# HGD_v0_2_-20200615.net
KiCad netlist of a schematic drawn in Altium Designer
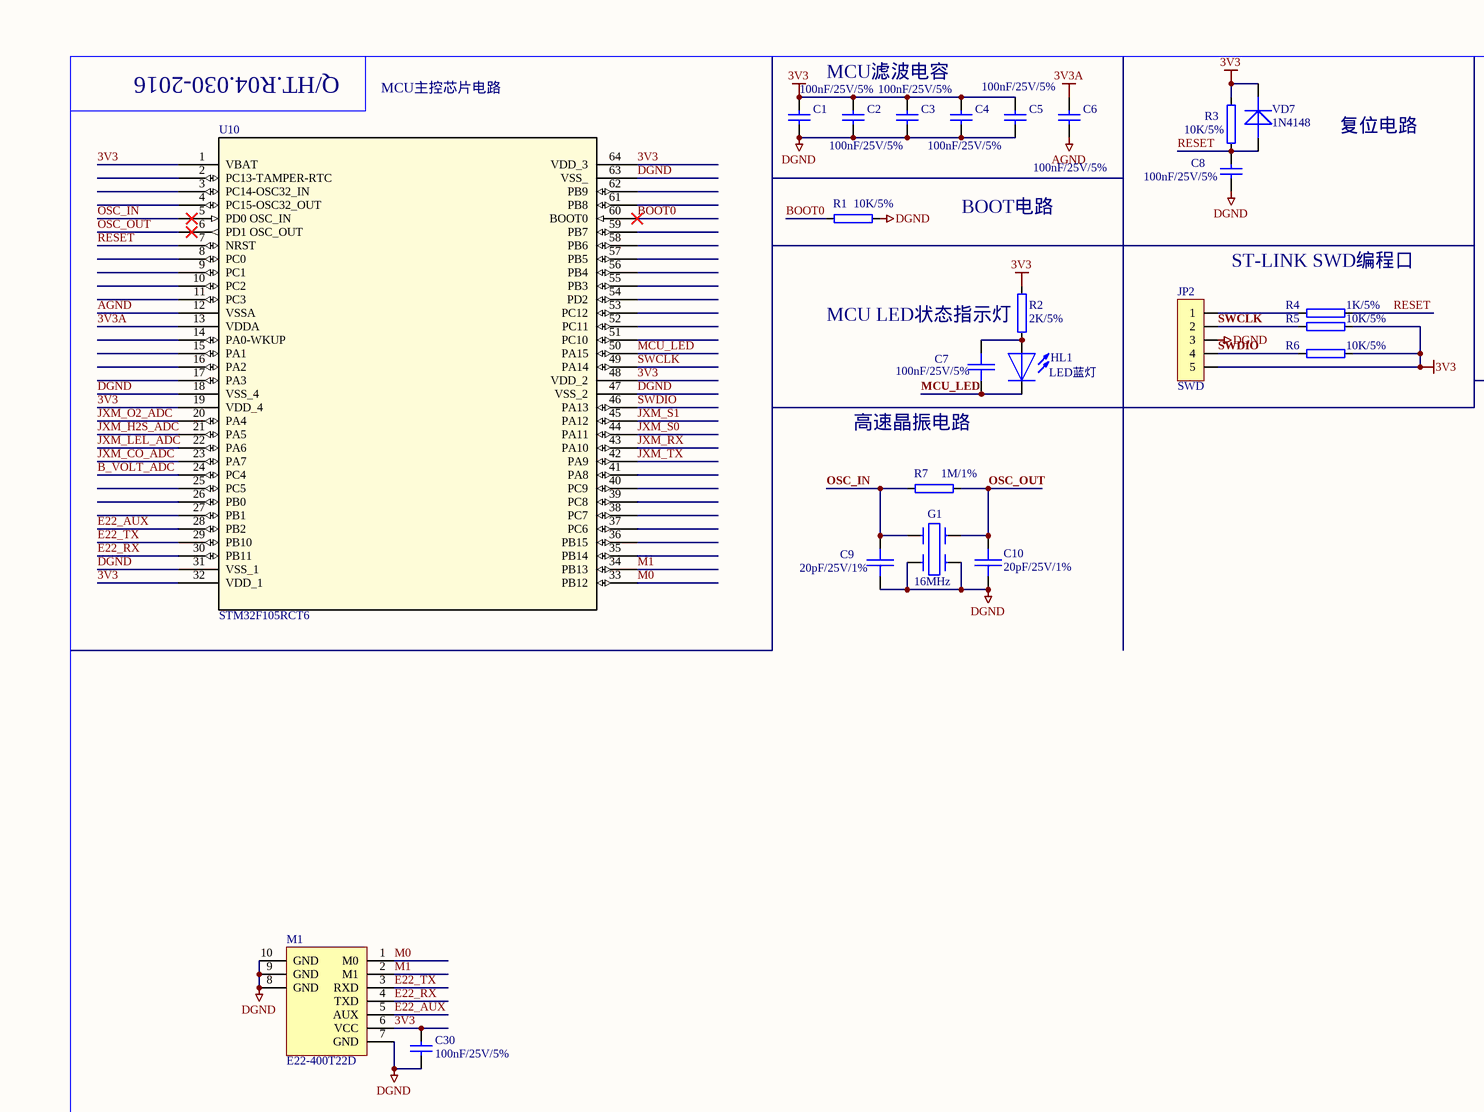
[diagram p0: HGD(v0.2)-20200615.SchDoc, top left]
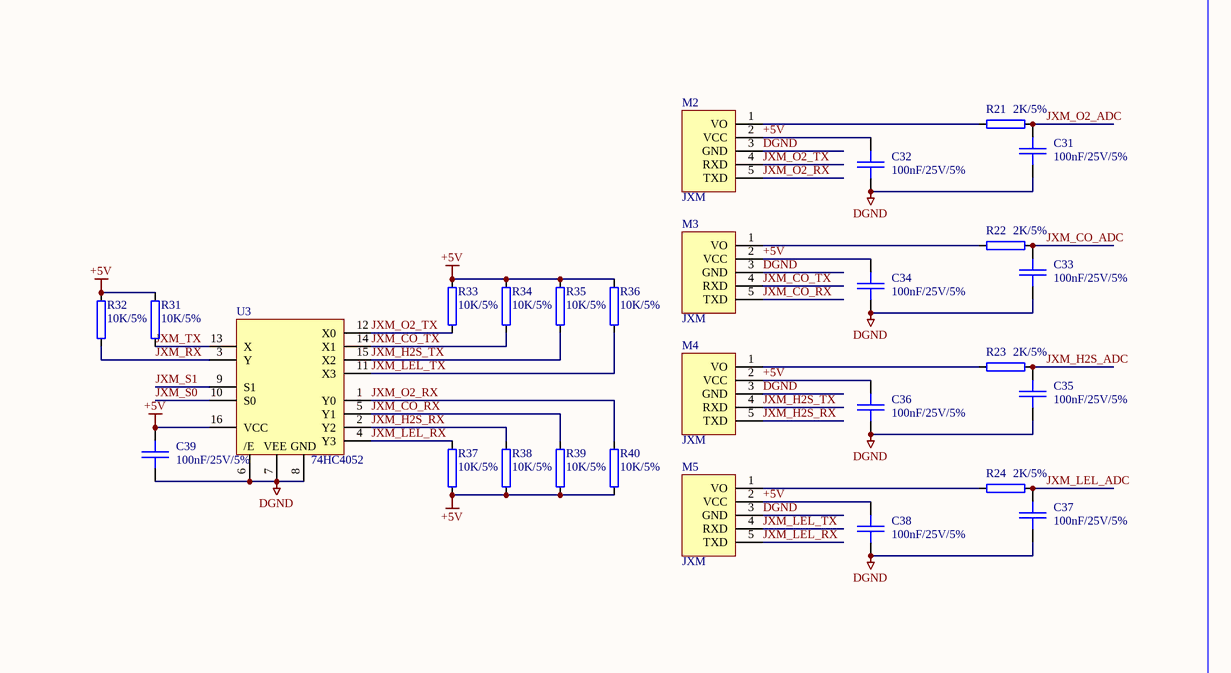
[diagram p1: HGD(v0.2)-20200615.SchDoc, top right]
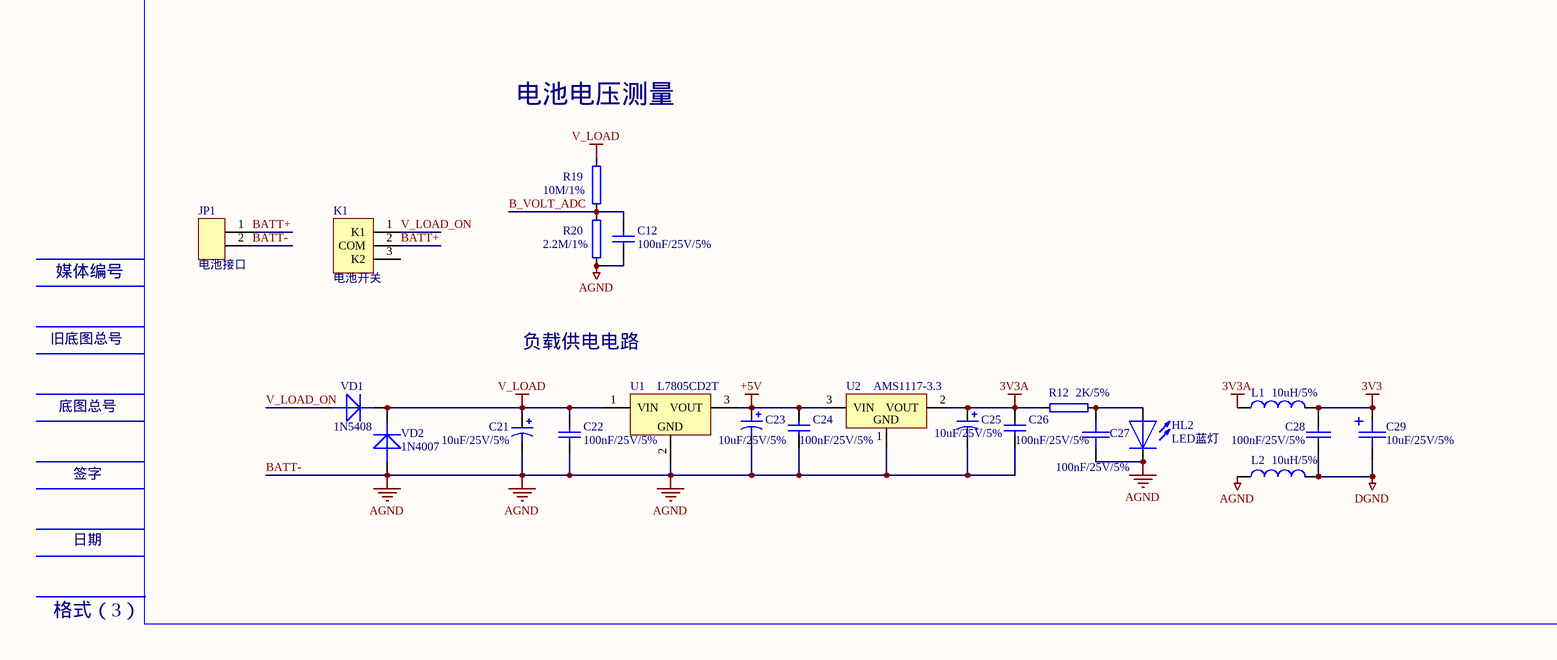
[diagram p2: HGD(v0.2)-20200615.SchDoc, bottom left]
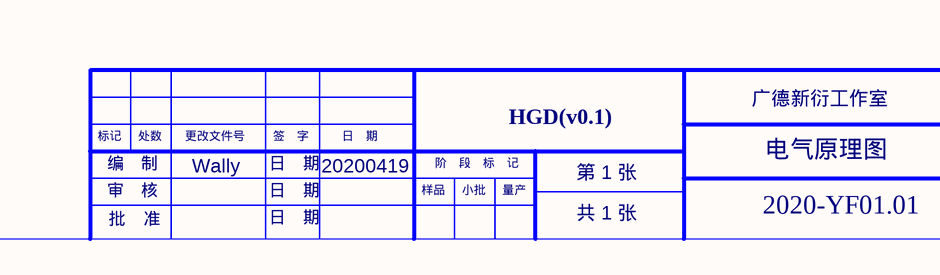
[diagram p3: HGD(v0.2)-20200615.SchDoc, bottom right]

(export (version "E")
  (design (tool "Eeschema 10.0.6"))
  (components
    (comp (ref "C1")
      (value "100nF/25V/5%")
      (footprint "C0603")
      (description "电容")
      (libsource (lib "*") (part "CAP-SMD"))
    )
    (comp (ref "C2")
      (value "100nF/25V/5%")
      (footprint "C0603")
      (description "电容")
      (libsource (lib "*") (part "CAP-SMD"))
    )
    (comp (ref "C3")
      (value "100nF/25V/5%")
      (footprint "C0603")
      (description "电容")
      (libsource (lib "*") (part "CAP-SMD"))
    )
    (comp (ref "C4")
      (value "100nF/25V/5%")
      (footprint "C0603")
      (description "电容")
      (libsource (lib "*") (part "CAP-SMD"))
    )
    (comp (ref "C5")
      (value "100nF/25V/5%")
      (footprint "C0603")
      (description "电容")
      (libsource (lib "*") (part "CAP-SMD"))
    )
    (comp (ref "C6")
      (value "100nF/25V/5%")
      (footprint "C0603")
      (description "电容")
      (libsource (lib "*") (part "CAP-SMD"))
    )
    (comp (ref "C7")
      (value "100nF/25V/5%")
      (footprint "C0603")
      (description "电容")
      (libsource (lib "*") (part "CAP"))
    )
    (comp (ref "C8")
      (value "100nF/25V/5%")
      (footprint "C0603")
      (description "电容")
      (libsource (lib "*") (part "CAP-SMD"))
    )
    (comp (ref "C9")
      (value "20pF/25V/1%")
      (footprint "C0603")
      (description "电容")
      (libsource (lib "ESSCH-Union") (part "CAP"))
    )
    (comp (ref "C10")
      (value "20pF/25V/1%")
      (footprint "C0603")
      (description "电容")
      (libsource (lib "ESSCH-Union") (part "CAP"))
    )
    (comp (ref "C12") (value "100nF/25V/5%") (footprint "C0603") (libsource (lib "*") (part "CAP-SMD")))
    (comp (ref "C21")
      (value "10uF/25V/5%")
      (footprint "C1206-1")
      (description "钽电容")
      (fields (field (name "PUBLISHER") "Altium Limited"))
      (libsource (lib "Miscellaneous Devices") (part "Cap Pol1"))
    )
    (comp (ref "C22")
      (value "100nF/25V/5%")
      (footprint "C0603")
      (description "电容")
      (fields (field (name "PUBLISHER") "Altium Limited"))
      (libsource (lib "Miscellaneous Devices") (part "Cap"))
    )
    (comp (ref "C23")
      (value "10uF/25V/5%")
      (footprint "C1206-1")
      (description "钽电容")
      (fields (field (name "PUBLISHER") "Altium Limited"))
      (libsource (lib "Miscellaneous Devices") (part "Cap Pol1"))
    )
    (comp (ref "C24")
      (value "100nF/25V/5%")
      (footprint "C0603")
      (description "电容")
      (fields (field (name "PUBLISHER") "Altium Limited"))
      (libsource (lib "Miscellaneous Devices") (part "Cap"))
    )
    (comp (ref "C25")
      (value "10uF/25V/5%")
      (footprint "C1206-1")
      (description "钽电容")
      (fields (field (name "PUBLISHER") "Altium Limited"))
      (libsource (lib "Miscellaneous Devices") (part "Cap Pol1"))
    )
    (comp (ref "C26")
      (value "100nF/25V/5%")
      (footprint "C0603")
      (description "电容")
      (fields (field (name "PUBLISHER") "Altium Limited"))
      (libsource (lib "Miscellaneous Devices") (part "Cap"))
    )
    (comp (ref "C27")
      (value "100nF/25V/5%")
      (footprint "C0603")
      (description "电容")
      (libsource (lib "*") (part "CAP"))
    )
    (comp (ref "C28")
      (value "100nF/25V/5%")
      (footprint "C0603")
      (description "电容")
      (libsource (lib "") (part "CAP_1"))
    )
    (comp (ref "C29")
      (value "10uF/25V/5%")
      (footprint "C1206-1")
      (description "钽电容")
      (libsource (lib "*") (part "ELECTRO1"))
    )
    (comp (ref "C30")
      (value "100nF/25V/5%")
      (footprint "C0603")
      (description "电容")
      (fields (field (name "PUBLISHER") "Altium Limited"))
      (libsource (lib "Miscellaneous Devices") (part "Cap"))
    )
    (comp (ref "C31")
      (value "100nF/25V/5%")
      (footprint "C0603")
      (description "电容")
      (libsource (lib "*") (part "CAP"))
    )
    (comp (ref "C32")
      (value "100nF/25V/5%")
      (footprint "C0603")
      (description "电容")
      (libsource (lib "*") (part "CAP"))
    )
    (comp (ref "C33")
      (value "100nF/25V/5%")
      (footprint "C0603")
      (description "电容")
      (libsource (lib "*") (part "CAP"))
    )
    (comp (ref "C34")
      (value "100nF/25V/5%")
      (footprint "C0603")
      (description "电容")
      (libsource (lib "*") (part "CAP"))
    )
    (comp (ref "C35")
      (value "100nF/25V/5%")
      (footprint "C0603")
      (description "电容")
      (libsource (lib "*") (part "CAP"))
    )
    (comp (ref "C36")
      (value "100nF/25V/5%")
      (footprint "C0603")
      (description "电容")
      (libsource (lib "*") (part "CAP"))
    )
    (comp (ref "C37")
      (value "100nF/25V/5%")
      (footprint "C0603")
      (description "电容")
      (libsource (lib "*") (part "CAP"))
    )
    (comp (ref "C38")
      (value "100nF/25V/5%")
      (footprint "C0603")
      (description "电容")
      (libsource (lib "*") (part "CAP"))
    )
    (comp (ref "C39")
      (value "100nF/25V/5%")
      (footprint "C0603")
      (description "电容")
      (libsource (lib "*") (part "CAP"))
    )
    (comp (ref "G1")
      (value "16MHz")
      (footprint "OSC5032")
      (description "两对电极压电晶体")
      (libsource (lib "ESSCH-Union") (part "CRYSTAL_4"))
    )
    (comp (ref "HL1")
      (value "LED蓝灯")
      (footprint "LED0603")
      (description "发光二极管")
      (libsource (lib "wypPCB_Lib") (part "发光二极管"))
    )
    (comp (ref "HL2")
      (value "LED蓝灯")
      (footprint "LED0603")
      (description "发光二极管")
      (libsource (lib "wypPCB_Lib") (part "发光二极管"))
    )
    (comp (ref "JP1")
      (value "电池接口")
      (footprint "XH2.54-LI-2P")
      (description "XH2.54-2P/PH2.0-2P插座")
      (libsource (lib "wypPCB_Lib") (part "XH2.54-2P/PH2.0-2P"))
    )
    (comp (ref "JP2")
      (value "SWD")
      (footprint "XH2.54-5AW")
      (description "XH2.54-5P直插插针")
      (libsource (lib "wypPCB_Lib") (part "JP_XH2.54-5AW"))
    )
    (comp (ref "K1")
      (value "电池开关")
      (footprint "SK-12D07")
      (description "SK-12D07：3脚2档小型拨动开关")
      (libsource (lib "wypPCB_Lib") (part "SK-12D07"))
    )
    (comp (ref "L1")
      (value "10uH/5%")
      (footprint "L0603")
      (description "电感")
      (libsource (lib "wypPCB_Lib") (part "电感"))
    )
    (comp (ref "L2")
      (value "10uH/5%")
      (footprint "L0603")
      (description "电感")
      (libsource (lib "wypPCB_Lib") (part "电感"))
    )
    (comp (ref "M1")
      (value "E22-400T22D")
      (footprint "E22-400T22D")
      (description "E22-400T22D LoRa模块")
      (libsource (lib "wypPCB_Lib") (part "E22-400T22D"))
    )
    (comp (ref "M2")
      (value "JXM")
      (footprint "JXM")
      (description "JXM智能气体模组传感器")
      (libsource (lib "wypPCB_Lib") (part "JXM"))
    )
    (comp (ref "M3")
      (value "JXM")
      (footprint "JXM")
      (description "JXM智能气体模组传感器")
      (libsource (lib "wypPCB_Lib") (part "JXM"))
    )
    (comp (ref "M4")
      (value "JXM")
      (footprint "JXM")
      (description "JXM智能气体模组传感器")
      (libsource (lib "wypPCB_Lib") (part "JXM"))
    )
    (comp (ref "M5")
      (value "JXM")
      (footprint "JXM")
      (description "JXM智能气体模组传感器")
      (libsource (lib "wypPCB_Lib") (part "JXM"))
    )
    (comp (ref "R1")
      (value "10K/5%")
      (footprint "R0603")
      (description "电阻")
      (libsource (lib "") (part "RES2_2"))
    )
    (comp (ref "R2")
      (value "2K/5%")
      (footprint "R0603")
      (description "电阻")
      (libsource (lib "") (part "RES2_2"))
    )
    (comp (ref "R3")
      (value "10K/5%")
      (footprint "R0603")
      (description "电阻")
      (libsource (lib "*") (part "RES2"))
    )
    (comp (ref "R4")
      (value "1K/5%")
      (footprint "R0603")
      (description "电阻")
      (libsource (lib "*") (part "RES2"))
    )
    (comp (ref "R5")
      (value "10K/5%")
      (footprint "R0603")
      (description "电阻")
      (libsource (lib "*") (part "RES2"))
    )
    (comp (ref "R6")
      (value "10K/5%")
      (footprint "R0603")
      (description "电阻")
      (libsource (lib "*") (part "RES2"))
    )
    (comp (ref "R7")
      (value "1M/1%")
      (footprint "R0603")
      (description "电阻")
      (libsource (lib "*") (part "RES2"))
    )
    (comp (ref "R12")
      (value "2K/5%")
      (footprint "R0603")
      (description "电阻")
      (libsource (lib "") (part "RES2_2"))
    )
    (comp (ref "R19")
      (value "10M/1%")
      (footprint "R0603")
      (description "电阻")
      (libsource (lib "") (part "RES2_2"))
    )
    (comp (ref "R20")
      (value "2.2M/1%")
      (footprint "R0603")
      (description "电阻")
      (libsource (lib "") (part "RES2_2"))
    )
    (comp (ref "R21")
      (value "2K/5%")
      (footprint "R0603")
      (description "电阻")
      (libsource (lib "") (part "RES2_2"))
    )
    (comp (ref "R22")
      (value "2K/5%")
      (footprint "R0603")
      (description "电阻")
      (libsource (lib "") (part "RES2_2"))
    )
    (comp (ref "R23")
      (value "2K/5%")
      (footprint "R0603")
      (description "电阻")
      (libsource (lib "") (part "RES2_2"))
    )
    (comp (ref "R24")
      (value "2K/5%")
      (footprint "R0603")
      (description "电阻")
      (libsource (lib "") (part "RES2_2"))
    )
    (comp (ref "R31")
      (value "10K/5%")
      (footprint "R0603")
      (description "电阻")
      (libsource (lib "") (part "RES2_1"))
    )
    (comp (ref "R32")
      (value "10K/5%")
      (footprint "R0603")
      (description "电阻")
      (libsource (lib "") (part "RES2_1"))
    )
    (comp (ref "R33")
      (value "10K/5%")
      (footprint "R0603")
      (description "电阻")
      (libsource (lib "") (part "RES2_1"))
    )
    (comp (ref "R34")
      (value "10K/5%")
      (footprint "R0603")
      (description "电阻")
      (libsource (lib "") (part "RES2_1"))
    )
    (comp (ref "R35")
      (value "10K/5%")
      (footprint "R0603")
      (description "电阻")
      (libsource (lib "") (part "RES2_1"))
    )
    (comp (ref "R36")
      (value "10K/5%")
      (footprint "R0603")
      (description "电阻")
      (libsource (lib "") (part "RES2_1"))
    )
    (comp (ref "R37")
      (value "10K/5%")
      (footprint "R0603")
      (description "电阻")
      (libsource (lib "") (part "RES2_1"))
    )
    (comp (ref "R38")
      (value "10K/5%")
      (footprint "R0603")
      (description "电阻")
      (libsource (lib "") (part "RES2_1"))
    )
    (comp (ref "R39")
      (value "10K/5%")
      (footprint "R0603")
      (description "电阻")
      (libsource (lib "") (part "RES2_1"))
    )
    (comp (ref "R40")
      (value "10K/5%")
      (footprint "R0603")
      (description "电阻")
      (libsource (lib "") (part "RES2_1"))
    )
    (comp (ref "U1")
      (value "L7805CD2T")
      (footprint "D2PAK")
      (description "Positive voltage regulator")
      (libsource (lib "wypPCB_Lib") (part "L7805CD2T"))
    )
    (comp (ref "U2")
      (value "AMS1117-3.3")
      (footprint "SOT230P700X180-4N")
      (description "U_AMS1117稳压芯片")
      (libsource (lib "wypPCB_Lib") (part "U_AMS1117"))
    )
    (comp (ref "U3")
      (value "74HC4052")
      (footprint "SO16_74HC4052")
      (libsource (lib "wypPCB_Lib") (part "74HC4052"))
    )
    (comp (ref "U10")
      (value "STM32F105RCT6")
      (footprint "LQFP64")
      (description "MCU")
      (fields
        (field (name "MANUFACTURER_PART_NUMBER") "STM32F103RCT6")
        (field (name "DIGIKEYPARTNUMBER") "497-9033-ND")
        (field (name "COPYRIGHT") "Copyright (C) 2015 Accelerated Designs. All rights reserved")
      )
      (libsource (lib "L14-Collect_board(v1.1)") (part "STM32F103RCT6"))
    )
    (comp (ref "VD1")
      (value "1N5408")
      (footprint "SMA_DO-214AC")
      (description "开关二极管")
      (libsource (lib "wypPCB_Lib") (part "开关二极管"))
    )
    (comp (ref "VD2")
      (value "1N4007")
      (footprint "SMA_DO-214AC")
      (description "开关二极管")
      (libsource (lib "wypPCB_Lib") (part "开关二极管"))
    )
    (comp (ref "VD7")
      (value "1N4148")
      (footprint "LL-34")
      (description "开关二极管")
      (libsource (lib "wypPCB_Lib") (part "开关二极管"))
    )
  )
  (nets
    (net (code "1") (name "+5V") (class "Default")
      (node (ref "C23") (pin "1") (pinfunction "1_1") (pintype "passive"))
      (node (ref "C24") (pin "2") (pinfunction "2_2") (pintype "passive"))
      (node (ref "C32") (pin "1") (pintype "passive"))
      (node (ref "C34") (pin "1") (pintype "passive"))
      (node (ref "C36") (pin "1") (pintype "passive"))
      (node (ref "C38") (pin "1") (pintype "passive"))
      (node (ref "C39") (pin "1") (pintype "passive"))
      (node (ref "M2") (pin "2") (pinfunction "VCC_2") (pintype "passive"))
      (node (ref "M3") (pin "2") (pinfunction "VCC_2") (pintype "passive"))
      (node (ref "M4") (pin "2") (pinfunction "VCC_2") (pintype "passive"))
      (node (ref "M5") (pin "2") (pinfunction "VCC_2") (pintype "passive"))
      (node (ref "R31") (pin "2") (pintype "passive"))
      (node (ref "R32") (pin "2") (pintype "passive"))
      (node (ref "R33") (pin "2") (pintype "passive"))
      (node (ref "R34") (pin "2") (pintype "passive"))
      (node (ref "R35") (pin "2") (pintype "passive"))
      (node (ref "R36") (pin "2") (pintype "passive"))
      (node (ref "R37") (pin "1") (pintype "passive"))
      (node (ref "R38") (pin "1") (pintype "passive"))
      (node (ref "R39") (pin "1") (pintype "passive"))
      (node (ref "R40") (pin "1") (pintype "passive"))
      (node (ref "U1") (pin "3") (pinfunction "VOUT_3") (pintype "passive"))
      (node (ref "U2") (pin "3") (pinfunction "VIN_3") (pintype "passive"))
      (node (ref "U3") (pin "16") (pinfunction "VCC_16") (pintype "passive"))
    )
    (net (code "2") (name "/BATT+") (class "Default")
      (node (ref "JP1") (pin "1") (pintype "passive"))
      (node (ref "K1") (pin "2") (pinfunction "COM_2") (pintype "passive"))
    )
    (net (code "3") (name "/BOOT0") (class "Default")
      (node (ref "R1") (pin "2") (pintype "passive"))
      (node (ref "U10") (pin "60") (pinfunction "BOOT0_60") (pintype "input"))
    )
    (net (code "4") (name "/B_VOLT_ADC") (class "Default")
      (node (ref "C12") (pin "1") (pintype "passive"))
      (node (ref "R19") (pin "2") (pintype "passive"))
      (node (ref "R20") (pin "1") (pintype "passive"))
      (node (ref "U10") (pin "24") (pinfunction "PC4_24") (pintype "bidirectional"))
    )
    (net (code "5") (name "/E22_AUX") (class "Default")
      (node (ref "M1") (pin "5") (pinfunction "AUX_5") (pintype "passive"))
      (node (ref "U10") (pin "28") (pinfunction "PB2_28") (pintype "bidirectional"))
    )
    (net (code "6") (name "/E22_RX") (class "Default")
      (node (ref "M1") (pin "4") (pinfunction "TXD_4") (pintype "passive"))
      (node (ref "U10") (pin "30") (pinfunction "PB11_30") (pintype "bidirectional"))
    )
    (net (code "7") (name "/E22_TX") (class "Default")
      (node (ref "M1") (pin "3") (pinfunction "RXD_3") (pintype "passive"))
      (node (ref "U10") (pin "29") (pinfunction "PB10_29") (pintype "bidirectional"))
    )
    (net (code "8") (name "/JXM_CO_ADC") (class "Default")
      (node (ref "C33") (pin "1") (pintype "passive"))
      (node (ref "R22") (pin "1") (pintype "passive"))
      (node (ref "U10") (pin "23") (pinfunction "PA7_23") (pintype "bidirectional"))
    )
    (net (code "9") (name "/JXM_CO_RX") (class "Default")
      (node (ref "M3") (pin "5") (pinfunction "TXD_5") (pintype "passive"))
      (node (ref "R39") (pin "2") (pintype "passive"))
      (node (ref "U3") (pin "5") (pinfunction "Y1_5") (pintype "passive"))
    )
    (net (code "10") (name "/JXM_CO_TX") (class "Default")
      (node (ref "M3") (pin "4") (pinfunction "RXD_4") (pintype "passive"))
      (node (ref "R34") (pin "1") (pintype "passive"))
      (node (ref "U3") (pin "14") (pinfunction "X1_14") (pintype "passive"))
    )
    (net (code "11") (name "/JXM_H2S_ADC") (class "Default")
      (node (ref "C35") (pin "1") (pintype "passive"))
      (node (ref "R23") (pin "1") (pintype "passive"))
      (node (ref "U10") (pin "21") (pinfunction "PA5_21") (pintype "bidirectional"))
    )
    (net (code "12") (name "/JXM_H2S_RX") (class "Default")
      (node (ref "M4") (pin "5") (pinfunction "TXD_5") (pintype "passive"))
      (node (ref "R38") (pin "2") (pintype "passive"))
      (node (ref "U3") (pin "2") (pinfunction "Y2_2") (pintype "passive"))
    )
    (net (code "13") (name "/JXM_H2S_TX") (class "Default")
      (node (ref "M4") (pin "4") (pinfunction "RXD_4") (pintype "passive"))
      (node (ref "R35") (pin "1") (pintype "passive"))
      (node (ref "U3") (pin "15") (pinfunction "X2_15") (pintype "passive"))
    )
    (net (code "14") (name "/JXM_LEL_ADC") (class "Default")
      (node (ref "C37") (pin "1") (pintype "passive"))
      (node (ref "R24") (pin "1") (pintype "passive"))
      (node (ref "U10") (pin "22") (pinfunction "PA6_22") (pintype "bidirectional"))
    )
    (net (code "15") (name "/JXM_LEL_RX") (class "Default")
      (node (ref "M5") (pin "5") (pinfunction "TXD_5") (pintype "passive"))
      (node (ref "R37") (pin "2") (pintype "passive"))
      (node (ref "U3") (pin "4") (pinfunction "Y3_4") (pintype "passive"))
    )
    (net (code "16") (name "/JXM_LEL_TX") (class "Default")
      (node (ref "M5") (pin "4") (pinfunction "RXD_4") (pintype "passive"))
      (node (ref "R36") (pin "1") (pintype "passive"))
      (node (ref "U3") (pin "11") (pinfunction "X3_11") (pintype "passive"))
    )
    (net (code "17") (name "/JXM_O2_ADC") (class "Default")
      (node (ref "C31") (pin "1") (pintype "passive"))
      (node (ref "R21") (pin "1") (pintype "passive"))
      (node (ref "U10") (pin "20") (pinfunction "PA4_20") (pintype "bidirectional"))
    )
    (net (code "18") (name "/JXM_O2_RX") (class "Default")
      (node (ref "M2") (pin "5") (pinfunction "TXD_5") (pintype "passive"))
      (node (ref "R40") (pin "2") (pintype "passive"))
      (node (ref "U3") (pin "1") (pinfunction "Y0_1") (pintype "passive"))
    )
    (net (code "19") (name "/JXM_O2_TX") (class "Default")
      (node (ref "M2") (pin "4") (pinfunction "RXD_4") (pintype "passive"))
      (node (ref "R33") (pin "1") (pintype "passive"))
      (node (ref "U3") (pin "12") (pinfunction "X0_12") (pintype "passive"))
    )
    (net (code "20") (name "/JXM_RX") (class "Default")
      (node (ref "R32") (pin "1") (pintype "passive"))
      (node (ref "U10") (pin "43") (pinfunction "PA10_43") (pintype "bidirectional"))
      (node (ref "U3") (pin "3") (pinfunction "Y_3") (pintype "passive"))
    )
    (net (code "21") (name "/JXM_S0") (class "Default")
      (node (ref "U10") (pin "44") (pinfunction "PA11_44") (pintype "bidirectional"))
      (node (ref "U3") (pin "10") (pinfunction "S0_10") (pintype "passive"))
    )
    (net (code "22") (name "/JXM_S1") (class "Default")
      (node (ref "U10") (pin "45") (pinfunction "PA12_45") (pintype "bidirectional"))
      (node (ref "U3") (pin "9") (pinfunction "S1_9") (pintype "passive"))
    )
    (net (code "23") (name "/JXM_TX") (class "Default")
      (node (ref "R31") (pin "1") (pintype "passive"))
      (node (ref "U10") (pin "42") (pinfunction "PA9_42") (pintype "bidirectional"))
      (node (ref "U3") (pin "13") (pinfunction "X_13") (pintype "passive"))
    )
    (net (code "24") (name "/M0") (class "Default")
      (node (ref "M1") (pin "1") (pinfunction "M0_1") (pintype "passive"))
      (node (ref "U10") (pin "33") (pinfunction "PB12_33") (pintype "bidirectional"))
    )
    (net (code "25") (name "/M1") (class "Default")
      (node (ref "M1") (pin "2") (pinfunction "M1_2") (pintype "passive"))
      (node (ref "U10") (pin "34") (pinfunction "PB13_34") (pintype "bidirectional"))
    )
    (net (code "26") (name "/MCU_LED") (class "Default")
      (node (ref "C7") (pin "2") (pintype "passive"))
      (node (ref "HL1") (pin "K") (pintype "passive"))
      (node (ref "U10") (pin "50") (pinfunction "PA15_50") (pintype "bidirectional"))
    )
    (net (code "27") (name "/OSC_IN") (class "Default")
      (node (ref "C9") (pin "2") (pintype "passive"))
      (node (ref "G1") (pin "1") (pintype "passive"))
      (node (ref "R7") (pin "1") (pintype "passive"))
      (node (ref "U10") (pin "5") (pinfunction "PD0_OSC_IN_5") (pintype "input"))
    )
    (net (code "28") (name "/OSC_OUT") (class "Default")
      (node (ref "C10") (pin "1") (pintype "passive"))
      (node (ref "G1") (pin "3") (pintype "passive"))
      (node (ref "R7") (pin "2") (pintype "passive"))
      (node (ref "U10") (pin "6") (pinfunction "PD1_OSC_OUT_6") (pintype "output"))
    )
    (net (code "29") (name "/RESET") (class "Default")
      (node (ref "C8") (pin "1") (pintype "passive"))
      (node (ref "R3") (pin "1") (pintype "passive"))
      (node (ref "R4") (pin "2") (pintype "passive"))
      (node (ref "U10") (pin "7") (pinfunction "NRST_7") (pintype "bidirectional"))
      (node (ref "VD7") (pin "A") (pintype "passive"))
    )
    (net (code "30") (name "/SWCLK") (class "Default")
      (node (ref "JP2") (pin "2") (pinfunction "2_2") (pintype "passive"))
      (node (ref "R5") (pin "1") (pintype "passive"))
      (node (ref "U10") (pin "49") (pinfunction "PA14_49") (pintype "bidirectional"))
    )
    (net (code "31") (name "/SWDIO") (class "Default")
      (node (ref "JP2") (pin "4") (pinfunction "4_4") (pintype "passive"))
      (node (ref "R6") (pin "1") (pintype "passive"))
      (node (ref "U10") (pin "46") (pinfunction "PA13_46") (pintype "bidirectional"))
    )
    (net (code "32") (name "/V_LOAD_ON") (class "Default")
      (node (ref "K1") (pin "1") (pinfunction "K1_1") (pintype "passive"))
      (node (ref "VD1") (pin "A") (pintype "passive"))
    )
    (net (code "33") (name "3V3") (class "Default")
      (node (ref "C1") (pin "2") (pintype "passive"))
      (node (ref "C2") (pin "1") (pintype "passive"))
      (node (ref "C28") (pin "2") (pintype "passive"))
      (node (ref "C29") (pin "1") (pintype "passive"))
      (node (ref "C3") (pin "1") (pintype "passive"))
      (node (ref "C30") (pin "2") (pinfunction "2_2") (pintype "passive"))
      (node (ref "C4") (pin "2") (pintype "passive"))
      (node (ref "C5") (pin "2") (pintype "passive"))
      (node (ref "JP2") (pin "5") (pinfunction "5_5") (pintype "passive"))
      (node (ref "L1") (pin "2") (pinfunction "2_2") (pintype "passive"))
      (node (ref "M1") (pin "6") (pinfunction "VCC_6") (pintype "passive"))
      (node (ref "R2") (pin "1") (pintype "passive"))
      (node (ref "R3") (pin "2") (pintype "passive"))
      (node (ref "R5") (pin "2") (pintype "passive"))
      (node (ref "R6") (pin "2") (pintype "passive"))
      (node (ref "U10") (pin "1") (pinfunction "VBAT_1") (pintype "power_in"))
      (node (ref "U10") (pin "19") (pinfunction "VDD_4_19") (pintype "power_in"))
      (node (ref "U10") (pin "32") (pinfunction "VDD_1_32") (pintype "power_in"))
      (node (ref "U10") (pin "48") (pinfunction "VDD_2_48") (pintype "power_in"))
      (node (ref "U10") (pin "64") (pinfunction "VDD_3_64") (pintype "power_in"))
      (node (ref "VD7") (pin "K") (pintype "passive"))
    )
    (net (code "34") (name "3V3A") (class "Default")
      (node (ref "C25") (pin "1") (pinfunction "1_1") (pintype "passive"))
      (node (ref "C26") (pin "2") (pinfunction "2_2") (pintype "passive"))
      (node (ref "C6") (pin "2") (pintype "passive"))
      (node (ref "L1") (pin "1") (pinfunction "1_1") (pintype "passive"))
      (node (ref "R12") (pin "1") (pintype "passive"))
      (node (ref "U10") (pin "13") (pinfunction "VDDA_13") (pintype "power_in"))
      (node (ref "U2") (pin "2") (pinfunction "VOUT_2") (pintype "passive"))
    )
    (net (code "35") (name "AGND") (class "Default")
      (node (ref "C12") (pin "2") (pintype "passive"))
      (node (ref "C21") (pin "2") (pinfunction "2_2") (pintype "passive"))
      (node (ref "C22") (pin "1") (pinfunction "1_1") (pintype "passive"))
      (node (ref "C23") (pin "2") (pinfunction "2_2") (pintype "passive"))
      (node (ref "C24") (pin "1") (pinfunction "1_1") (pintype "passive"))
      (node (ref "C25") (pin "2") (pinfunction "2_2") (pintype "passive"))
      (node (ref "C26") (pin "1") (pinfunction "1_1") (pintype "passive"))
      (node (ref "C27") (pin "2") (pintype "passive"))
      (node (ref "C6") (pin "1") (pintype "passive"))
      (node (ref "HL2") (pin "K") (pintype "passive"))
      (node (ref "JP1") (pin "2") (pintype "passive"))
      (node (ref "L2") (pin "1") (pinfunction "1_1") (pintype "passive"))
      (node (ref "R20") (pin "2") (pintype "passive"))
      (node (ref "U1") (pin "2") (pinfunction "GND_2") (pintype "passive"))
      (node (ref "U10") (pin "12") (pinfunction "VSSA_12") (pintype "power_in"))
      (node (ref "U2") (pin "1") (pinfunction "GND_1") (pintype "passive"))
      (node (ref "VD2") (pin "A") (pintype "passive"))
    )
    (net (code "36") (name "DGND") (class "Default")
      (node (ref "C1") (pin "1") (pintype "passive"))
      (node (ref "C10") (pin "2") (pintype "passive"))
      (node (ref "C2") (pin "2") (pintype "passive"))
      (node (ref "C28") (pin "1") (pintype "passive"))
      (node (ref "C29") (pin "2") (pintype "passive"))
      (node (ref "C3") (pin "2") (pintype "passive"))
      (node (ref "C30") (pin "1") (pinfunction "1_1") (pintype "passive"))
      (node (ref "C31") (pin "2") (pintype "passive"))
      (node (ref "C32") (pin "2") (pintype "passive"))
      (node (ref "C33") (pin "2") (pintype "passive"))
      (node (ref "C34") (pin "2") (pintype "passive"))
      (node (ref "C35") (pin "2") (pintype "passive"))
      (node (ref "C36") (pin "2") (pintype "passive"))
      (node (ref "C37") (pin "2") (pintype "passive"))
      (node (ref "C38") (pin "2") (pintype "passive"))
      (node (ref "C39") (pin "2") (pintype "passive"))
      (node (ref "C4") (pin "1") (pintype "passive"))
      (node (ref "C5") (pin "1") (pintype "passive"))
      (node (ref "C8") (pin "2") (pintype "passive"))
      (node (ref "C9") (pin "1") (pintype "passive"))
      (node (ref "G1") (pin "2") (pintype "passive"))
      (node (ref "G1") (pin "4") (pintype "passive"))
      (node (ref "JP2") (pin "3") (pinfunction "3_3") (pintype "passive"))
      (node (ref "L2") (pin "2") (pinfunction "2_2") (pintype "passive"))
      (node (ref "M1") (pin "10") (pinfunction "GND_10") (pintype "passive"))
      (node (ref "M1") (pin "7") (pinfunction "GND_7") (pintype "passive"))
      (node (ref "M1") (pin "8") (pinfunction "GND_8") (pintype "passive"))
      (node (ref "M1") (pin "9") (pinfunction "GND_9") (pintype "passive"))
      (node (ref "M2") (pin "3") (pinfunction "GND_3") (pintype "passive"))
      (node (ref "M3") (pin "3") (pinfunction "GND_3") (pintype "passive"))
      (node (ref "M4") (pin "3") (pinfunction "GND_3") (pintype "passive"))
      (node (ref "M5") (pin "3") (pinfunction "GND_3") (pintype "passive"))
      (node (ref "R1") (pin "1") (pintype "passive"))
      (node (ref "U10") (pin "18") (pinfunction "VSS_4_18") (pintype "power_in"))
      (node (ref "U10") (pin "31") (pinfunction "VSS_1_31") (pintype "power_in"))
      (node (ref "U10") (pin "47") (pinfunction "VSS_2_47") (pintype "power_in"))
      (node (ref "U10") (pin "63") (pinfunction "VSS__63") (pintype "power_in"))
      (node (ref "U3") (pin "6") (pinfunction "~{E}_6") (pintype "passive"))
      (node (ref "U3") (pin "7") (pinfunction "VEE_7") (pintype "passive"))
      (node (ref "U3") (pin "8") (pinfunction "GND_8") (pintype "passive"))
    )
    (net (code "37") (name "Net-(C7-Pad1)") (class "Default")
      (node (ref "C7") (pin "1") (pintype "passive"))
      (node (ref "HL1") (pin "A") (pintype "passive"))
      (node (ref "R2") (pin "2") (pintype "passive"))
    )
    (net (code "38") (name "Net-(C27-Pad1)") (class "Default")
      (node (ref "C27") (pin "1") (pintype "passive"))
      (node (ref "HL2") (pin "A") (pintype "passive"))
      (node (ref "R12") (pin "2") (pintype "passive"))
    )
    (net (code "39") (name "Net-(JP2-Pad1)") (class "Default")
      (node (ref "JP2") (pin "1") (pinfunction "1_1") (pintype "passive"))
      (node (ref "R4") (pin "1") (pintype "passive"))
    )
    (net (code "40") (name "Net-(M2-VO)") (class "Default")
      (node (ref "M2") (pin "1") (pinfunction "VO_1") (pintype "passive"))
      (node (ref "R21") (pin "2") (pintype "passive"))
    )
    (net (code "41") (name "Net-(M3-VO)") (class "Default")
      (node (ref "M3") (pin "1") (pinfunction "VO_1") (pintype "passive"))
      (node (ref "R22") (pin "2") (pintype "passive"))
    )
    (net (code "42") (name "Net-(M4-VO)") (class "Default")
      (node (ref "M4") (pin "1") (pinfunction "VO_1") (pintype "passive"))
      (node (ref "R23") (pin "2") (pintype "passive"))
    )
    (net (code "43") (name "Net-(M5-VO)") (class "Default")
      (node (ref "M5") (pin "1") (pinfunction "VO_1") (pintype "passive"))
      (node (ref "R24") (pin "2") (pintype "passive"))
    )
    (net (code "44") (name "V_LOAD") (class "Default")
      (node (ref "C21") (pin "1") (pinfunction "1_1") (pintype "passive"))
      (node (ref "C22") (pin "2") (pinfunction "2_2") (pintype "passive"))
      (node (ref "R19") (pin "1") (pintype "passive"))
      (node (ref "U1") (pin "1") (pinfunction "VIN_1") (pintype "passive"))
      (node (ref "VD1") (pin "K") (pintype "passive"))
      (node (ref "VD2") (pin "K") (pintype "passive"))
    )
    (net (code "45") (name "unconnected-(K1-K2-Pad3)") (class "Default")
      (node (ref "K1") (pin "3") (pinfunction "K2_3") (pintype "passive"))
    )
    (net (code "46") (name "unconnected-(U10-PA0-WKUP-Pad14)") (class "Default")
      (node (ref "U10") (pin "14") (pinfunction "PA0-WKUP_14") (pintype "bidirectional"))
    )
    (net (code "47") (name "unconnected-(U10-PA1-Pad15)") (class "Default")
      (node (ref "U10") (pin "15") (pinfunction "PA1_15") (pintype "bidirectional"))
    )
    (net (code "48") (name "unconnected-(U10-PA2-Pad16)") (class "Default")
      (node (ref "U10") (pin "16") (pinfunction "PA2_16") (pintype "bidirectional"))
    )
    (net (code "49") (name "unconnected-(U10-PA3-Pad17)") (class "Default")
      (node (ref "U10") (pin "17") (pinfunction "PA3_17") (pintype "bidirectional"))
    )
    (net (code "50") (name "unconnected-(U10-PA8-Pad41)") (class "Default")
      (node (ref "U10") (pin "41") (pinfunction "PA8_41") (pintype "bidirectional"))
    )
    (net (code "51") (name "unconnected-(U10-PB0-Pad26)") (class "Default")
      (node (ref "U10") (pin "26") (pinfunction "PB0_26") (pintype "bidirectional"))
    )
    (net (code "52") (name "unconnected-(U10-PB1-Pad27)") (class "Default")
      (node (ref "U10") (pin "27") (pinfunction "PB1_27") (pintype "bidirectional"))
    )
    (net (code "53") (name "unconnected-(U10-PB3-Pad55)") (class "Default")
      (node (ref "U10") (pin "55") (pinfunction "PB3_55") (pintype "bidirectional"))
    )
    (net (code "54") (name "unconnected-(U10-PB4-Pad56)") (class "Default")
      (node (ref "U10") (pin "56") (pinfunction "PB4_56") (pintype "bidirectional"))
    )
    (net (code "55") (name "unconnected-(U10-PB5-Pad57)") (class "Default")
      (node (ref "U10") (pin "57") (pinfunction "PB5_57") (pintype "bidirectional"))
    )
    (net (code "56") (name "unconnected-(U10-PB6-Pad58)") (class "Default")
      (node (ref "U10") (pin "58") (pinfunction "PB6_58") (pintype "bidirectional"))
    )
    (net (code "57") (name "unconnected-(U10-PB7-Pad59)") (class "Default")
      (node (ref "U10") (pin "59") (pinfunction "PB7_59") (pintype "bidirectional"))
    )
    (net (code "58") (name "unconnected-(U10-PB8-Pad61)") (class "Default")
      (node (ref "U10") (pin "61") (pinfunction "PB8_61") (pintype "bidirectional"))
    )
    (net (code "59") (name "unconnected-(U10-PB9-Pad62)") (class "Default")
      (node (ref "U10") (pin "62") (pinfunction "PB9_62") (pintype "bidirectional"))
    )
    (net (code "60") (name "unconnected-(U10-PB14-Pad35)") (class "Default")
      (node (ref "U10") (pin "35") (pinfunction "PB14_35") (pintype "bidirectional"))
    )
    (net (code "61") (name "unconnected-(U10-PB15-Pad36)") (class "Default")
      (node (ref "U10") (pin "36") (pinfunction "PB15_36") (pintype "bidirectional"))
    )
    (net (code "62") (name "unconnected-(U10-PC0-Pad8)") (class "Default")
      (node (ref "U10") (pin "8") (pinfunction "PC0_8") (pintype "bidirectional"))
    )
    (net (code "63") (name "unconnected-(U10-PC1-Pad9)") (class "Default")
      (node (ref "U10") (pin "9") (pinfunction "PC1_9") (pintype "bidirectional"))
    )
    (net (code "64") (name "unconnected-(U10-PC2-Pad10)") (class "Default")
      (node (ref "U10") (pin "10") (pinfunction "PC2_10") (pintype "bidirectional"))
    )
    (net (code "65") (name "unconnected-(U10-PC3-Pad11)") (class "Default")
      (node (ref "U10") (pin "11") (pinfunction "PC3_11") (pintype "bidirectional"))
    )
    (net (code "66") (name "unconnected-(U10-PC5-Pad25)") (class "Default")
      (node (ref "U10") (pin "25") (pinfunction "PC5_25") (pintype "bidirectional"))
    )
    (net (code "67") (name "unconnected-(U10-PC6-Pad37)") (class "Default")
      (node (ref "U10") (pin "37") (pinfunction "PC6_37") (pintype "bidirectional"))
    )
    (net (code "68") (name "unconnected-(U10-PC7-Pad38)") (class "Default")
      (node (ref "U10") (pin "38") (pinfunction "PC7_38") (pintype "bidirectional"))
    )
    (net (code "69") (name "unconnected-(U10-PC8-Pad39)") (class "Default")
      (node (ref "U10") (pin "39") (pinfunction "PC8_39") (pintype "bidirectional"))
    )
    (net (code "70") (name "unconnected-(U10-PC9-Pad40)") (class "Default")
      (node (ref "U10") (pin "40") (pinfunction "PC9_40") (pintype "bidirectional"))
    )
    (net (code "71") (name "unconnected-(U10-PC10-Pad51)") (class "Default")
      (node (ref "U10") (pin "51") (pinfunction "PC10_51") (pintype "bidirectional"))
    )
    (net (code "72") (name "unconnected-(U10-PC11-Pad52)") (class "Default")
      (node (ref "U10") (pin "52") (pinfunction "PC11_52") (pintype "bidirectional"))
    )
    (net (code "73") (name "unconnected-(U10-PC12-Pad53)") (class "Default")
      (node (ref "U10") (pin "53") (pinfunction "PC12_53") (pintype "bidirectional"))
    )
    (net (code "74") (name "unconnected-(U10-PC13-TAMPER-RTC-Pad2)") (class "Default")
      (node (ref "U10") (pin "2") (pinfunction "PC13-TAMPER-RTC_2") (pintype "bidirectional"))
    )
    (net (code "75") (name "unconnected-(U10-PC14-OSC32_IN-Pad3)") (class "Default")
      (node (ref "U10") (pin "3") (pinfunction "PC14-OSC32_IN_3") (pintype "bidirectional"))
    )
    (net (code "76") (name "unconnected-(U10-PC15-OSC32_OUT-Pad4)") (class "Default")
      (node (ref "U10") (pin "4") (pinfunction "PC15-OSC32_OUT_4") (pintype "bidirectional"))
    )
    (net (code "77") (name "unconnected-(U10-PD2-Pad54)") (class "Default")
      (node (ref "U10") (pin "54") (pinfunction "PD2_54") (pintype "bidirectional"))
    )
  )
)
